# LDR2.net
KiCad netlist of a schematic drawn in EAGLE
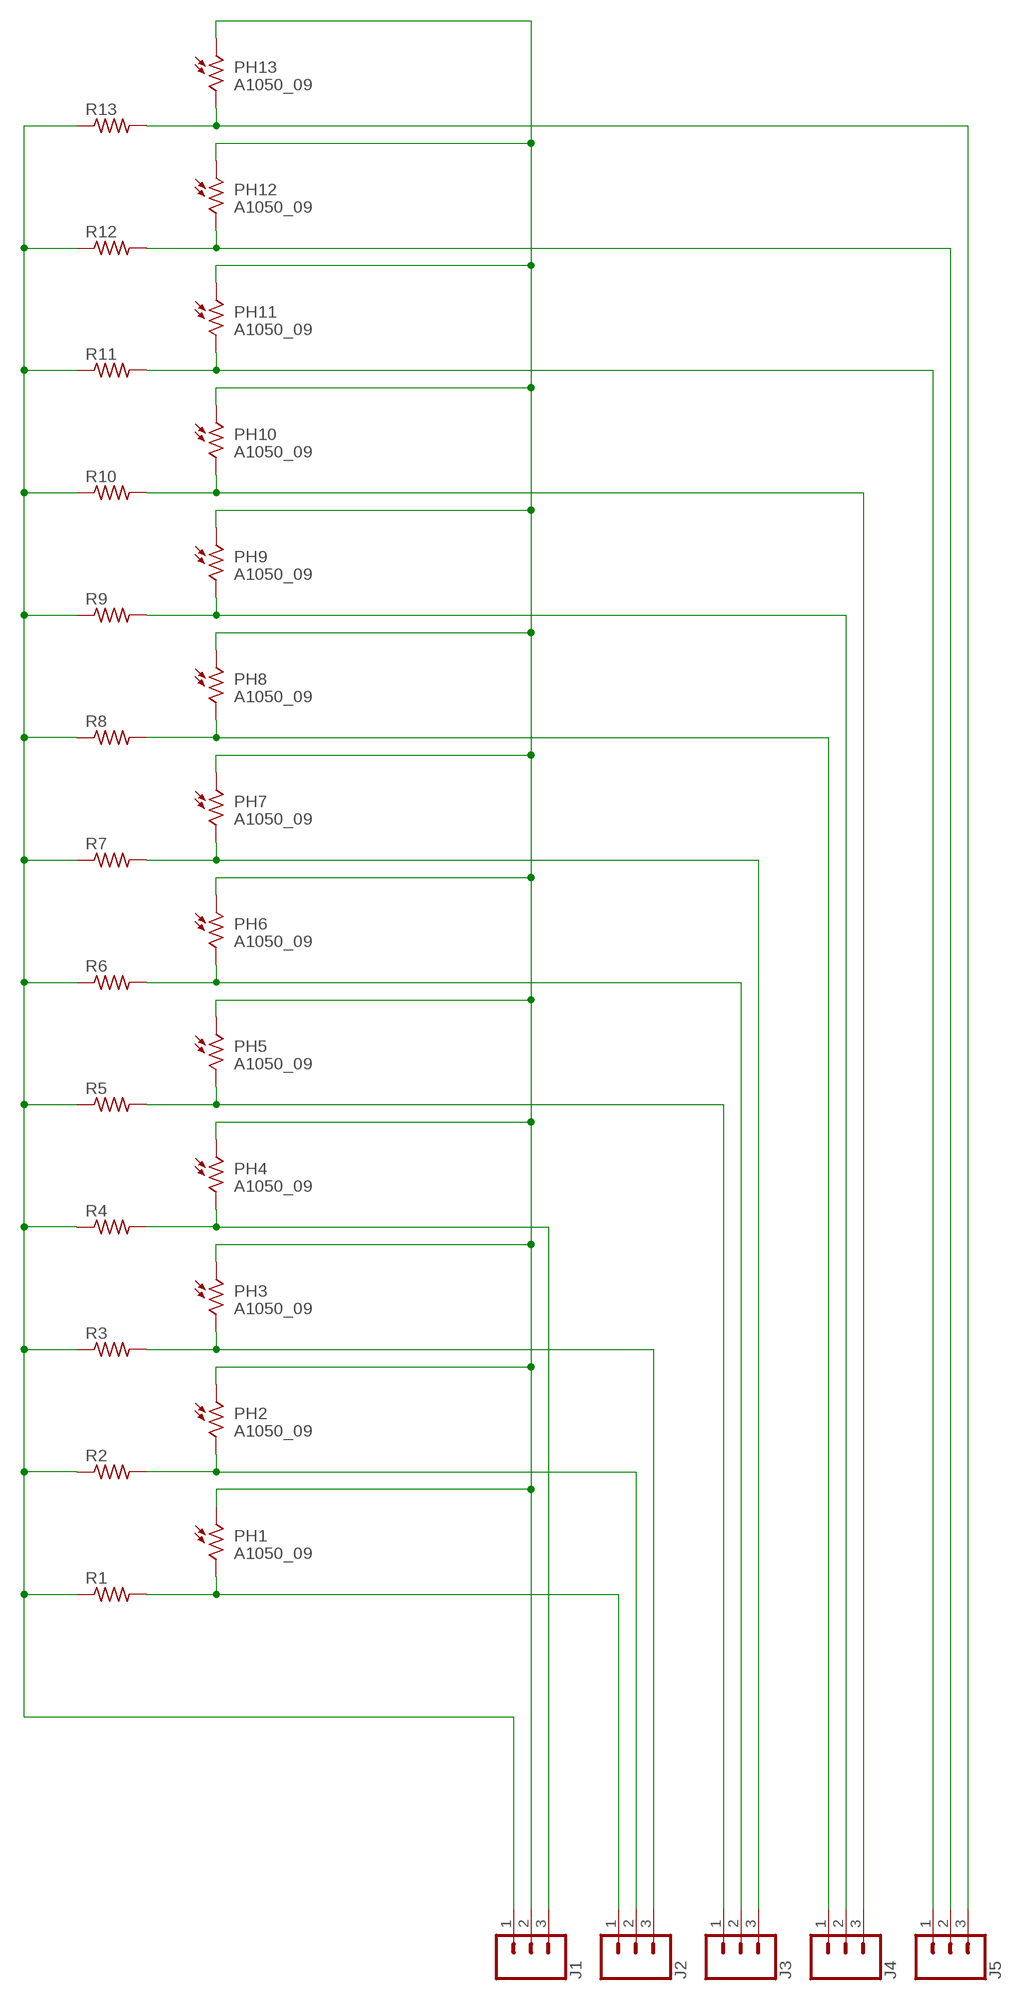
[diagram p0: schematic, sheet 1]

(export (version "E")
  (design (tool "Eeschema 10.0.6"))
  (components
    (comp (ref "J1")
      (value "CONN_03LONGPADS")
      (footprint "eagle-import:1X03_LONGPADS")
      (libsource (lib "eagle-import") (part "CONN_03LONGPADS"))
    )
    (comp (ref "J2")
      (value "CONN_03LONGPADS")
      (footprint "eagle-import:1X03_LONGPADS")
      (libsource (lib "eagle-import") (part "CONN_03LONGPADS"))
    )
    (comp (ref "J3")
      (value "CONN_03LONGPADS")
      (footprint "eagle-import:1X03_LONGPADS")
      (libsource (lib "eagle-import") (part "CONN_03LONGPADS"))
    )
    (comp (ref "J4")
      (value "CONN_03LONGPADS")
      (footprint "eagle-import:1X03_LONGPADS")
      (libsource (lib "eagle-import") (part "CONN_03LONGPADS"))
    )
    (comp (ref "J5")
      (value "CONN_03LONGPADS")
      (footprint "eagle-import:1X03_LONGPADS")
      (libsource (lib "eagle-import") (part "CONN_03LONGPADS"))
    )
    (comp (ref "PH1")
      (value "A1050_09")
      (footprint "eagle-import:T0-46-A10XX")
      (libsource (lib "eagle-import") (part "A1050_09"))
    )
    (comp (ref "PH2")
      (value "A1050_09")
      (footprint "eagle-import:T0-46-A10XX")
      (libsource (lib "eagle-import") (part "A1050_09"))
    )
    (comp (ref "PH3")
      (value "A1050_09")
      (footprint "eagle-import:T0-46-A10XX")
      (libsource (lib "eagle-import") (part "A1050_09"))
    )
    (comp (ref "PH4")
      (value "A1050_09")
      (footprint "eagle-import:T0-46-A10XX")
      (libsource (lib "eagle-import") (part "A1050_09"))
    )
    (comp (ref "PH5")
      (value "A1050_09")
      (footprint "eagle-import:T0-46-A10XX")
      (libsource (lib "eagle-import") (part "A1050_09"))
    )
    (comp (ref "PH6")
      (value "A1050_09")
      (footprint "eagle-import:T0-46-A10XX")
      (libsource (lib "eagle-import") (part "A1050_09"))
    )
    (comp (ref "PH7")
      (value "A1050_09")
      (footprint "eagle-import:T0-46-A10XX")
      (libsource (lib "eagle-import") (part "A1050_09"))
    )
    (comp (ref "PH8")
      (value "A1050_09")
      (footprint "eagle-import:T0-46-A10XX")
      (libsource (lib "eagle-import") (part "A1050_09"))
    )
    (comp (ref "PH9")
      (value "A1050_09")
      (footprint "eagle-import:T0-46-A10XX")
      (libsource (lib "eagle-import") (part "A1050_09"))
    )
    (comp (ref "PH10")
      (value "A1050_09")
      (footprint "eagle-import:T0-46-A10XX")
      (libsource (lib "eagle-import") (part "A1050_09"))
    )
    (comp (ref "PH11")
      (value "A1050_09")
      (footprint "eagle-import:T0-46-A10XX")
      (libsource (lib "eagle-import") (part "A1050_09"))
    )
    (comp (ref "PH12")
      (value "A1050_09")
      (footprint "eagle-import:T0-46-A10XX")
      (libsource (lib "eagle-import") (part "A1050_09"))
    )
    (comp (ref "PH13")
      (value "A1050_09")
      (footprint "eagle-import:T0-46-A10XX")
      (libsource (lib "eagle-import") (part "A1050_09"))
    )
    (comp (ref "R1")
      (value "R-US_0204/7")
      (footprint "eagle-import:0204_7")
      (libsource (lib "eagle-import") (part "R-US_0204/7"))
    )
    (comp (ref "R2")
      (value "R-US_0204/7")
      (footprint "eagle-import:0204_7")
      (libsource (lib "eagle-import") (part "R-US_0204/7"))
    )
    (comp (ref "R3")
      (value "R-US_0204/7")
      (footprint "eagle-import:0204_7")
      (libsource (lib "eagle-import") (part "R-US_0204/7"))
    )
    (comp (ref "R4")
      (value "R-US_0204/7")
      (footprint "eagle-import:0204_7")
      (libsource (lib "eagle-import") (part "R-US_0204/7"))
    )
    (comp (ref "R5")
      (value "R-US_0204/7")
      (footprint "eagle-import:0204_7")
      (libsource (lib "eagle-import") (part "R-US_0204/7"))
    )
    (comp (ref "R6")
      (value "R-US_0204/7")
      (footprint "eagle-import:0204_7")
      (libsource (lib "eagle-import") (part "R-US_0204/7"))
    )
    (comp (ref "R7")
      (value "R-US_0204/7")
      (footprint "eagle-import:0204_7")
      (libsource (lib "eagle-import") (part "R-US_0204/7"))
    )
    (comp (ref "R8")
      (value "R-US_0204/7")
      (footprint "eagle-import:0204_7")
      (libsource (lib "eagle-import") (part "R-US_0204/7"))
    )
    (comp (ref "R9")
      (value "R-US_0204/7")
      (footprint "eagle-import:0204_7")
      (libsource (lib "eagle-import") (part "R-US_0204/7"))
    )
    (comp (ref "R10")
      (value "R-US_0204/7")
      (footprint "eagle-import:0204_7")
      (libsource (lib "eagle-import") (part "R-US_0204/7"))
    )
    (comp (ref "R11")
      (value "R-US_0204/7")
      (footprint "eagle-import:0204_7")
      (libsource (lib "eagle-import") (part "R-US_0204/7"))
    )
    (comp (ref "R12")
      (value "R-US_0204/7")
      (footprint "eagle-import:0204_7")
      (libsource (lib "eagle-import") (part "R-US_0204/7"))
    )
    (comp (ref "R13")
      (value "R-US_0204/7")
      (footprint "eagle-import:0204_7")
      (libsource (lib "eagle-import") (part "R-US_0204/7"))
    )
  )
  (nets
    (net (code "1") (name "Net-(J1-Pad1)") (class "Default")
      (node (ref "J1") (pin "1") (pinfunction "1_1") (pintype "passive"))
      (node (ref "R1") (pin "1") (pinfunction "1_1") (pintype "passive"))
      (node (ref "R10") (pin "1") (pinfunction "1_1") (pintype "passive"))
      (node (ref "R11") (pin "1") (pinfunction "1_1") (pintype "passive"))
      (node (ref "R12") (pin "1") (pinfunction "1_1") (pintype "passive"))
      (node (ref "R13") (pin "1") (pinfunction "1_1") (pintype "passive"))
      (node (ref "R2") (pin "1") (pinfunction "1_1") (pintype "passive"))
      (node (ref "R3") (pin "1") (pinfunction "1_1") (pintype "passive"))
      (node (ref "R4") (pin "1") (pinfunction "1_1") (pintype "passive"))
      (node (ref "R5") (pin "1") (pinfunction "1_1") (pintype "passive"))
      (node (ref "R6") (pin "1") (pinfunction "1_1") (pintype "passive"))
      (node (ref "R7") (pin "1") (pinfunction "1_1") (pintype "passive"))
      (node (ref "R8") (pin "1") (pinfunction "1_1") (pintype "passive"))
      (node (ref "R9") (pin "1") (pinfunction "1_1") (pintype "passive"))
    )
    (net (code "2") (name "Net-(J1-Pad2)") (class "Default")
      (node (ref "J1") (pin "2") (pinfunction "2_2") (pintype "passive"))
      (node (ref "PH1") (pin "1") (pinfunction "1_1") (pintype "passive"))
      (node (ref "PH10") (pin "1") (pinfunction "1_1") (pintype "passive"))
      (node (ref "PH11") (pin "1") (pinfunction "1_1") (pintype "passive"))
      (node (ref "PH12") (pin "1") (pinfunction "1_1") (pintype "passive"))
      (node (ref "PH13") (pin "1") (pinfunction "1_1") (pintype "passive"))
      (node (ref "PH2") (pin "1") (pinfunction "1_1") (pintype "passive"))
      (node (ref "PH3") (pin "1") (pinfunction "1_1") (pintype "passive"))
      (node (ref "PH4") (pin "1") (pinfunction "1_1") (pintype "passive"))
      (node (ref "PH5") (pin "1") (pinfunction "1_1") (pintype "passive"))
      (node (ref "PH6") (pin "1") (pinfunction "1_1") (pintype "passive"))
      (node (ref "PH7") (pin "1") (pinfunction "1_1") (pintype "passive"))
      (node (ref "PH8") (pin "1") (pinfunction "1_1") (pintype "passive"))
      (node (ref "PH9") (pin "1") (pinfunction "1_1") (pintype "passive"))
    )
    (net (code "3") (name "Net-(J1-Pad3)") (class "Default")
      (node (ref "J1") (pin "3") (pinfunction "3_3") (pintype "passive"))
      (node (ref "PH4") (pin "2") (pinfunction "2_2") (pintype "passive"))
      (node (ref "R4") (pin "2") (pinfunction "2_2") (pintype "passive"))
    )
    (net (code "4") (name "Net-(J2-Pad1)") (class "Default")
      (node (ref "J2") (pin "1") (pinfunction "1_1") (pintype "passive"))
      (node (ref "PH1") (pin "2") (pinfunction "2_2") (pintype "passive"))
      (node (ref "R1") (pin "2") (pinfunction "2_2") (pintype "passive"))
    )
    (net (code "5") (name "Net-(J2-Pad2)") (class "Default")
      (node (ref "J2") (pin "2") (pinfunction "2_2") (pintype "passive"))
      (node (ref "PH2") (pin "2") (pinfunction "2_2") (pintype "passive"))
      (node (ref "R2") (pin "2") (pinfunction "2_2") (pintype "passive"))
    )
    (net (code "6") (name "Net-(J2-Pad3)") (class "Default")
      (node (ref "J2") (pin "3") (pinfunction "3_3") (pintype "passive"))
      (node (ref "PH3") (pin "2") (pinfunction "2_2") (pintype "passive"))
      (node (ref "R3") (pin "2") (pinfunction "2_2") (pintype "passive"))
    )
    (net (code "7") (name "Net-(J3-Pad1)") (class "Default")
      (node (ref "J3") (pin "1") (pinfunction "1_1") (pintype "passive"))
      (node (ref "PH5") (pin "2") (pinfunction "2_2") (pintype "passive"))
      (node (ref "R5") (pin "2") (pinfunction "2_2") (pintype "passive"))
    )
    (net (code "8") (name "Net-(J3-Pad2)") (class "Default")
      (node (ref "J3") (pin "2") (pinfunction "2_2") (pintype "passive"))
      (node (ref "PH6") (pin "2") (pinfunction "2_2") (pintype "passive"))
      (node (ref "R6") (pin "2") (pinfunction "2_2") (pintype "passive"))
    )
    (net (code "9") (name "Net-(J3-Pad3)") (class "Default")
      (node (ref "J3") (pin "3") (pinfunction "3_3") (pintype "passive"))
      (node (ref "PH7") (pin "2") (pinfunction "2_2") (pintype "passive"))
      (node (ref "R7") (pin "2") (pinfunction "2_2") (pintype "passive"))
    )
    (net (code "10") (name "Net-(J4-Pad1)") (class "Default")
      (node (ref "J4") (pin "1") (pinfunction "1_1") (pintype "passive"))
      (node (ref "PH8") (pin "2") (pinfunction "2_2") (pintype "passive"))
      (node (ref "R8") (pin "2") (pinfunction "2_2") (pintype "passive"))
    )
    (net (code "11") (name "Net-(J4-Pad2)") (class "Default")
      (node (ref "J4") (pin "2") (pinfunction "2_2") (pintype "passive"))
      (node (ref "PH9") (pin "2") (pinfunction "2_2") (pintype "passive"))
      (node (ref "R9") (pin "2") (pinfunction "2_2") (pintype "passive"))
    )
    (net (code "12") (name "Net-(J4-Pad3)") (class "Default")
      (node (ref "J4") (pin "3") (pinfunction "3_3") (pintype "passive"))
      (node (ref "PH10") (pin "2") (pinfunction "2_2") (pintype "passive"))
      (node (ref "R10") (pin "2") (pinfunction "2_2") (pintype "passive"))
    )
    (net (code "13") (name "Net-(J5-Pad1)") (class "Default")
      (node (ref "J5") (pin "1") (pinfunction "1_1") (pintype "passive"))
      (node (ref "PH11") (pin "2") (pinfunction "2_2") (pintype "passive"))
      (node (ref "R11") (pin "2") (pinfunction "2_2") (pintype "passive"))
    )
    (net (code "14") (name "Net-(J5-Pad2)") (class "Default")
      (node (ref "J5") (pin "2") (pinfunction "2_2") (pintype "passive"))
      (node (ref "PH12") (pin "2") (pinfunction "2_2") (pintype "passive"))
      (node (ref "R12") (pin "2") (pinfunction "2_2") (pintype "passive"))
    )
    (net (code "15") (name "Net-(J5-Pad3)") (class "Default")
      (node (ref "J5") (pin "3") (pinfunction "3_3") (pintype "passive"))
      (node (ref "PH13") (pin "2") (pinfunction "2_2") (pintype "passive"))
      (node (ref "R13") (pin "2") (pinfunction "2_2") (pintype "passive"))
    )
  )
)
